# connector.net
KiCad netlist of a schematic drawn in EAGLE
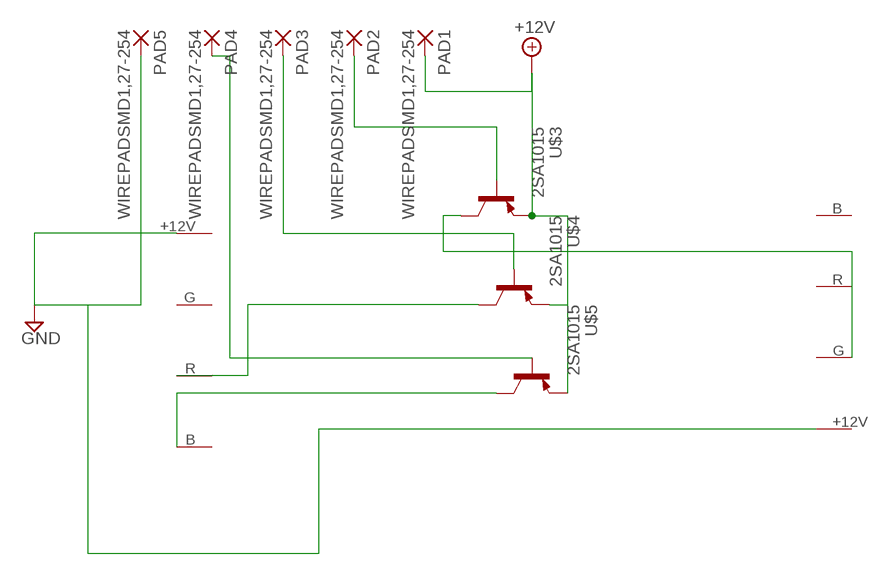
[diagram p0: schematic, sheet 1]

(export (version "E")
  (design (tool "Eeschema 10.0.6"))
  (components
    (comp (ref "PAD1")
      (value "WIREPADSMD1,27-254")
      (footprint "eagle-import:SMD1,27-2,54")
      (libsource (lib "eagle-import") (part "WIREPADSMD1,27-254"))
    )
    (comp (ref "PAD2")
      (value "WIREPADSMD1,27-254")
      (footprint "eagle-import:SMD1,27-2,54")
      (libsource (lib "eagle-import") (part "WIREPADSMD1,27-254"))
    )
    (comp (ref "PAD3")
      (value "WIREPADSMD1,27-254")
      (footprint "eagle-import:SMD1,27-2,54")
      (libsource (lib "eagle-import") (part "WIREPADSMD1,27-254"))
    )
    (comp (ref "PAD4")
      (value "WIREPADSMD1,27-254")
      (footprint "eagle-import:SMD1,27-2,54")
      (libsource (lib "eagle-import") (part "WIREPADSMD1,27-254"))
    )
    (comp (ref "PAD5")
      (value "WIREPADSMD1,27-254")
      (footprint "eagle-import:SMD1,27-2,54")
      (libsource (lib "eagle-import") (part "WIREPADSMD1,27-254"))
    )
    (comp (ref "U$1")
      (value "LED_STRIP_SOLDER_PAD")
      (footprint "eagle-import:STRIP")
      (libsource (lib "eagle-import") (part "LED_STRIP_SOLDER_PAD"))
    )
    (comp (ref "U$2")
      (value "LED_STRIP_SOLDER_PAD")
      (footprint "eagle-import:STRIP")
      (libsource (lib "eagle-import") (part "LED_STRIP_SOLDER_PAD"))
    )
    (comp (ref "U$3")
      (value "2SA1015")
      (footprint "eagle-import:TO92-EBC")
      (libsource (lib "eagle-import") (part "2SA1015"))
    )
    (comp (ref "U$4")
      (value "2SA1015")
      (footprint "eagle-import:TO92-EBC")
      (libsource (lib "eagle-import") (part "2SA1015"))
    )
    (comp (ref "U$5")
      (value "2SA1015")
      (footprint "eagle-import:TO92-EBC")
      (libsource (lib "eagle-import") (part "2SA1015"))
    )
  )
  (nets
    (net (code "1") (name "+12V") (class "Default")
      (node (ref "PAD1") (pin "1") (pinfunction "P_1") (pintype "passive"))
      (node (ref "U$3") (pin "E") (pinfunction "E_E") (pintype "passive"))
      (node (ref "U$4") (pin "E") (pinfunction "E_E") (pintype "passive"))
      (node (ref "U$5") (pin "E") (pinfunction "E_E") (pintype "passive"))
    )
    (net (code "2") (name "GND") (class "Default")
      (node (ref "PAD5") (pin "1") (pinfunction "P_1") (pintype "passive"))
      (node (ref "U$2") (pin "+12V") (pinfunction "+12V_+12V") (pintype "bidirectional"))
    )
    (net (code "3") (name "Net-(PAD2-P)") (class "Default")
      (node (ref "PAD2") (pin "1") (pinfunction "P_1") (pintype "passive"))
      (node (ref "U$3") (pin "B") (pinfunction "B_B") (pintype "passive"))
    )
    (net (code "4") (name "Net-(PAD3-P)") (class "Default")
      (node (ref "PAD3") (pin "1") (pinfunction "P_1") (pintype "passive"))
      (node (ref "U$4") (pin "B") (pinfunction "B_B") (pintype "passive"))
    )
    (net (code "5") (name "Net-(PAD4-P)") (class "Default")
      (node (ref "PAD4") (pin "1") (pinfunction "P_1") (pintype "passive"))
      (node (ref "U$5") (pin "B") (pinfunction "B_B") (pintype "passive"))
    )
    (net (code "6") (name "Net-(U$1-PadG)") (class "Default")
      (node (ref "U$1") (pin "G") (pinfunction "G_G") (pintype "bidirectional"))
      (node (ref "U$3") (pin "C") (pinfunction "C_C") (pintype "passive"))
    )
    (net (code "7") (name "Net-(U$2-PadB)") (class "Default")
      (node (ref "U$2") (pin "B") (pinfunction "B_B") (pintype "bidirectional"))
      (node (ref "U$5") (pin "C") (pinfunction "C_C") (pintype "passive"))
    )
    (net (code "8") (name "Net-(U$2-PadR)") (class "Default")
      (node (ref "U$2") (pin "R") (pinfunction "R_R") (pintype "bidirectional"))
      (node (ref "U$4") (pin "C") (pinfunction "C_C") (pintype "passive"))
    )
    (net (code "9") (name "unconnected-(U$1-Pad+12V)") (class "Default")
      (node (ref "U$1") (pin "+12V") (pinfunction "+12V_+12V") (pintype "bidirectional"))
    )
    (net (code "10") (name "unconnected-(U$1-PadB)") (class "Default")
      (node (ref "U$1") (pin "B") (pinfunction "B_B") (pintype "bidirectional"))
    )
    (net (code "11") (name "unconnected-(U$1-PadR)") (class "Default")
      (node (ref "U$1") (pin "R") (pinfunction "R_R") (pintype "bidirectional"))
    )
    (net (code "12") (name "unconnected-(U$2-PadG)") (class "Default")
      (node (ref "U$2") (pin "G") (pinfunction "G_G") (pintype "bidirectional"))
    )
  )
)
